# MZ.net
KiCad netlist of a schematic drawn in Altium Designer
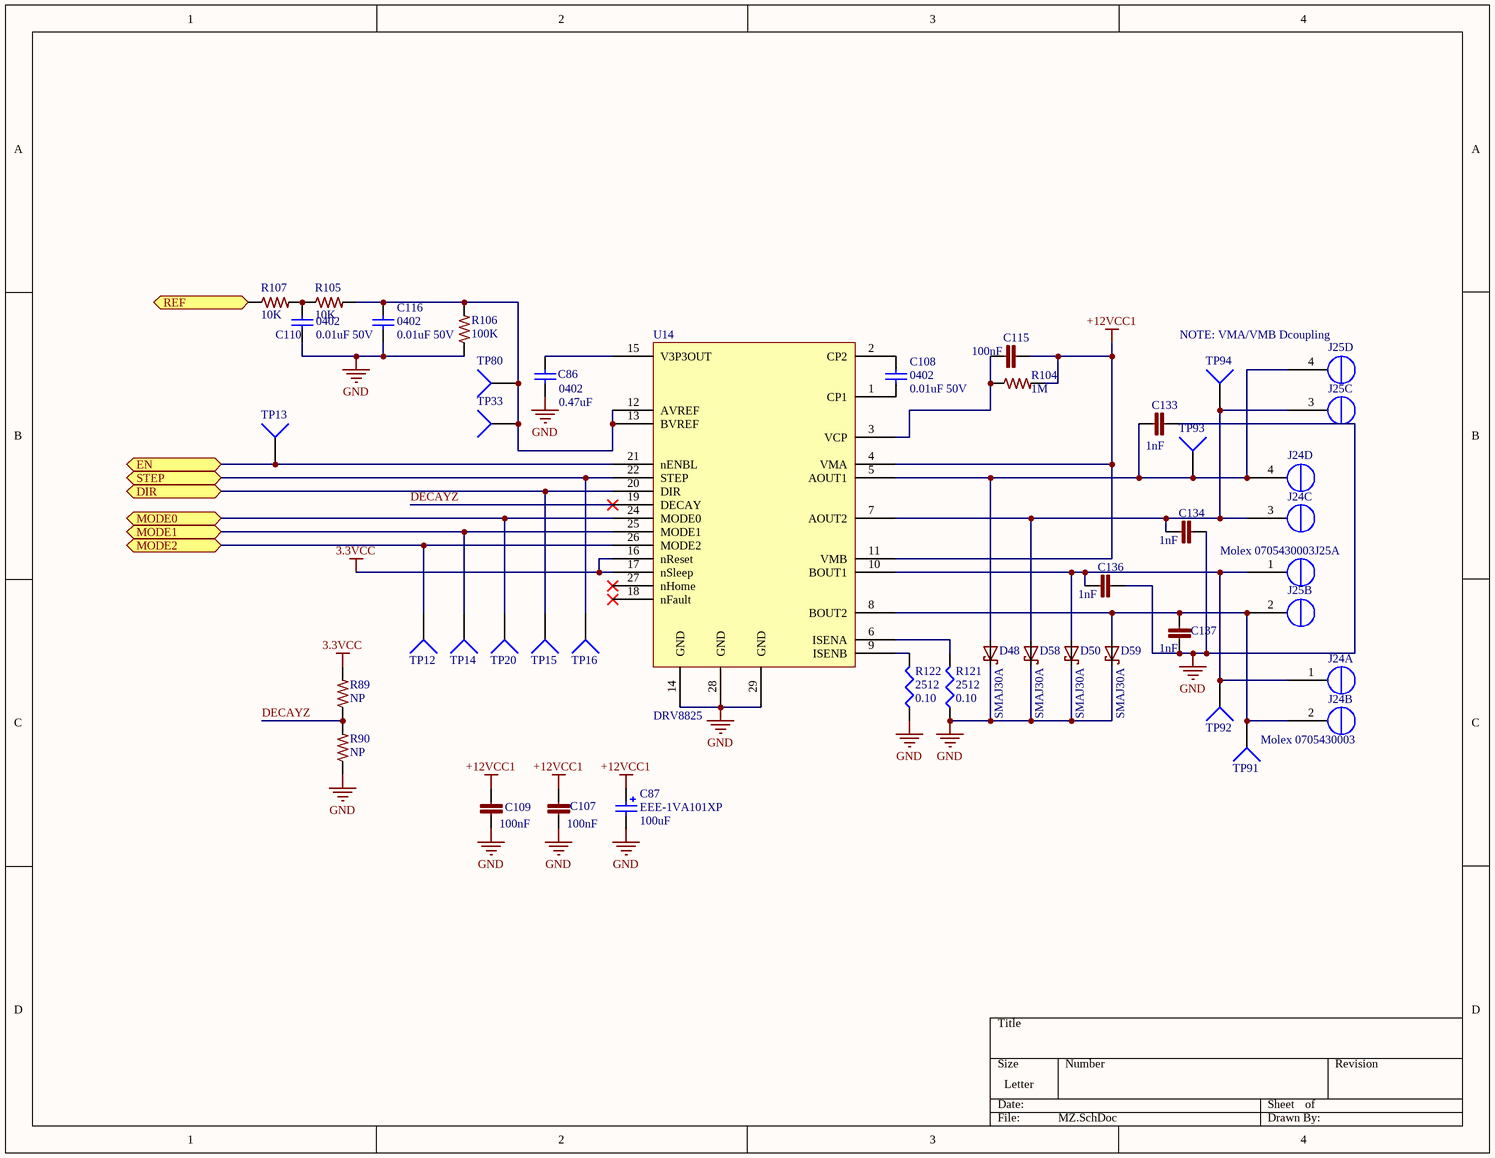
[diagram p0: MZ.SchDoc]

(export (version "E")
  (design (tool "Eeschema 10.0.6"))
  (components
    (comp (ref "C86")
      (value "0.47uF")
      (footprint "3Delight:C0402")
      (description "0.47uF 6.3v C0402 - GRM155R60J474KE19D")
      (fields
        (field (name "MFR PART #") "GRM155R60J474KE19D")
        (field (name "MFR") "Murata")
        (field (name "PACKAGEREFERENCE") "0402")
        (field (name "PUBLISHER") "Ultimachine")
      )
      (libsource (lib "Tigershark3D") (part "GRM155R60J474KE19D"))
    )
    (comp (ref "C87")
      (value "EEE-1VA101XP")
      (footprint "EEE-1VA101XP")
      (description "CAP ALUM 100UF 35V 20% SMD")
      (fields (field (name "DIGIKEY PART #") "PCE3951CT-ND") (field (name "ALTIUM_VALUE") "100uF"))
      (libsource (lib "Tigershark3D") (part "EEE-1VA101XP"))
    )
    (comp (ref "C107")
      (value "100nF")
      (footprint "C0603")
      (description "CAP CER 0603 100nF 50V 10% X7R")
      (fields
        (field (name "MANUFACTURERPARTNUMBER") "C0603C104K5RACTU")
        (field (name "PUBLISHER") "UltiMachine")
      )
      (libsource (lib "3Delight") (part "C0603C104K5RACTU"))
    )
    (comp (ref "C108")
      (value "0.01uF 50V")
      (footprint "C0402")
      (description "CAP CER 10000PF 50V X7R 0402")
      (fields
        (field (name "MFR PART #") "GRM155R71H103JA88D")
        (field (name "MFR") "Murata")
        (field (name "PACKAGEREFERENCE") "0402")
        (field (name "PUBLISHER") "Ultimachine")
      )
      (libsource (lib "Tigershark3D") (part "GRM155R71H103JA88D"))
    )
    (comp (ref "C109")
      (value "100nF")
      (footprint "C0603")
      (description "CAP CER 0603 100nF 50V 10% X7R")
      (fields
        (field (name "MANUFACTURERPARTNUMBER") "C0603C104K5RACTU")
        (field (name "PUBLISHER") "UltiMachine")
      )
      (libsource (lib "3Delight") (part "C0603C104K5RACTU"))
    )
    (comp (ref "C110")
      (value "0.01uF 50V")
      (footprint "C0402")
      (description "CAP CER 10000PF 50V X7R 0402")
      (fields
        (field (name "MFR PART #") "GRM155R71H103JA88D")
        (field (name "MFR") "Murata")
        (field (name "PACKAGEREFERENCE") "0402")
        (field (name "PUBLISHER") "Ultimachine")
      )
      (libsource (lib "Tigershark3D") (part "GRM155R71H103JA88D"))
    )
    (comp (ref "C115")
      (value "100nF")
      (footprint "C0402")
      (description "CAP CER 0402 100nF 16V 10% X7R")
      (fields
        (field (name "MANUFACTURERPARTNUMBER") "GRM155R71C104KA88D")
        (field (name "PUBLISHER") "UltiMachine")
      )
      (libsource (lib "3Delight") (part "GRM155R71C104KA88D"))
    )
    (comp (ref "C116")
      (value "0.01uF 50V")
      (footprint "C0402")
      (description "CAP CER 10000PF 50V X7R 0402")
      (fields
        (field (name "MFR PART #") "GRM155R71H103JA88D")
        (field (name "MFR") "Murata")
        (field (name "PACKAGEREFERENCE") "0402")
        (field (name "PUBLISHER") "Ultimachine")
      )
      (libsource (lib "Tigershark3D") (part "GRM155R71H103JA88D"))
    )
    (comp (ref "C133")
      (value "1nF")
      (footprint "C0603")
      (description "CAP CER 0603  1nF 50v 10% X7R")
      (fields
        (field (name "MANUFACTURERPARTNUMBER") "C0603C102K5RACTU")
        (field (name "PUBLISHER") "UltiMachine")
      )
      (libsource (lib "") (part "C0603C102K5RACTU_1"))
    )
    (comp (ref "C134")
      (value "1nF")
      (footprint "C0603")
      (description "CAP CER 0603  1nF 50v 10% X7R")
      (fields
        (field (name "MANUFACTURERPARTNUMBER") "C0603C102K5RACTU")
        (field (name "PUBLISHER") "UltiMachine")
      )
      (libsource (lib "") (part "C0603C102K5RACTU_1"))
    )
    (comp (ref "C136")
      (value "1nF")
      (footprint "C0603")
      (description "CAP CER 0603  1nF 50v 10% X7R")
      (fields
        (field (name "MANUFACTURERPARTNUMBER") "C0603C102K5RACTU")
        (field (name "PUBLISHER") "UltiMachine")
      )
      (libsource (lib "") (part "C0603C102K5RACTU_1"))
    )
    (comp (ref "C137")
      (value "1nF")
      (footprint "C0603")
      (description "CAP CER 0603  1nF 50v 10% X7R")
      (fields
        (field (name "MANUFACTURERPARTNUMBER") "C0603C102K5RACTU")
        (field (name "PUBLISHER") "UltiMachine")
      )
      (libsource (lib "3Delight") (part "C0603C102K5RACTU"))
    )
    (comp (ref "D48")
      (value "SMAJ30A")
      (footprint "SMA-SM")
      (description "DIODE TVS 30V SMA")
      (fields (field (name "PUBLISHER") "UltiMachine"))
      (libsource (lib "3Delight") (part "SMAJ30A"))
    )
    (comp (ref "D50")
      (value "SMAJ30A")
      (footprint "SMA-SM")
      (description "DIODE TVS 30V SMA")
      (fields (field (name "PUBLISHER") "UltiMachine"))
      (libsource (lib "3Delight") (part "SMAJ30A"))
    )
    (comp (ref "D58")
      (value "SMAJ30A")
      (footprint "SMA-SM")
      (description "DIODE TVS 30V SMA")
      (fields (field (name "PUBLISHER") "UltiMachine"))
      (libsource (lib "3Delight") (part "SMAJ30A"))
    )
    (comp (ref "D59")
      (value "SMAJ30A")
      (footprint "SMA-SM")
      (description "DIODE TVS 30V SMA")
      (fields (field (name "PUBLISHER") "UltiMachine"))
      (libsource (lib "3Delight") (part "SMAJ30A"))
    )
    (comp (ref "J24")
      (value "Molex 0705430003")
      (footprint "4POL254")
      (description "Molex 4 Pin Clip Connector")
      (libsource (lib "ZMBo Schematic Library") (part "Molex 0705430003 Alt"))
    )
    (comp (ref "J25")
      (value "Molex 0705430003")
      (footprint "4POL254")
      (description "Molex 4 Pin Clip Connector")
      (libsource (lib "ZMBo Schematic Library") (part "Molex 0705430003 Alt"))
    )
    (comp (ref "R89")
      (value "NP")
      (footprint "R0402")
      (description "Resistor")
      (fields (field (name "PUBLISHER") "UltiMachine"))
      (libsource (lib "3Delight") (part "Resistor"))
    )
    (comp (ref "R90")
      (value "NP")
      (footprint "R0402")
      (description "Resistor")
      (fields (field (name "PUBLISHER") "UltiMachine"))
      (libsource (lib "3Delight") (part "Resistor"))
    )
    (comp (ref "R104")
      (value "1M")
      (footprint "R0402")
      (description "RES 0402 1M 100mW 5%")
      (fields (field (name "MANUFACTURERPARTNUMBER") "ERJ2GEJ105X") (field (name "PUBLISHER") "UltiMachine"))
      (libsource (lib "3Delight") (part "ERJ2GEJ105X"))
    )
    (comp (ref "R105")
      (value "10K")
      (footprint "R0402")
      (description "RES SMD 10K OHM 1% 1/16W 0402")
      (fields
        (field (name "MANUFACTURERPARTNUMBER") "RC0402FR-0710KP")
        (field (name "PUBLISHER") "UltiMachine")
      )
      (libsource (lib "3Delight") (part "RC0402FR-0710KP"))
    )
    (comp (ref "R106")
      (value "100K")
      (footprint "R0402")
      (description "RES SMD 100K OHM 1% 1/16W 0402")
      (fields
        (field (name "MANUFACTURER") "Samsung")
        (field (name "MANUFACTURERPARTNUMBER") "RC1005F104CS")
        (field (name "PUBLISHER") "UltiMachine")
      )
      (libsource (lib "Tigershark3D") (part "RC1005F104CS"))
    )
    (comp (ref "R107")
      (value "10K")
      (footprint "R0402")
      (description "RES SMD 10K OHM 1% 1/16W 0402")
      (fields
        (field (name "MANUFACTURERPARTNUMBER") "RC0402FR-0710KP")
        (field (name "PUBLISHER") "UltiMachine")
      )
      (libsource (lib "3Delight") (part "RC0402FR-0710KP"))
    )
    (comp (ref "R121")
      (value "2512")
      (footprint "2512R-0.55")
      (description "RES SMD 0.1 OHM 1% 2W 2512")
      (fields (field (name "MFR") "Stackpole ELectronics Inc") (field (name "ALTIUM_VALUE") "0.10"))
      (libsource (lib "Tigershark3D") (part "CSRN2512FTR100"))
    )
    (comp (ref "R122")
      (value "2512")
      (footprint "2512R-0.55")
      (description "RES SMD 0.1 OHM 1% 2W 2512")
      (fields (field (name "MFR") "Stackpole ELectronics Inc") (field (name "ALTIUM_VALUE") "0.10"))
      (libsource (lib "Tigershark3D") (part "CSRN2512FTR100"))
    )
    (comp (ref "TP12")
      (value "TP4")
      (footprint "TP-2")
      (description "Socket")
      (fields (field (name "PUBLISHER") "Altium Limited"))
      (libsource (lib "ZMBo Schematic Library") (part "Socket"))
    )
    (comp (ref "TP13")
      (value "TP4")
      (footprint "TP-2")
      (description "Socket")
      (fields (field (name "PUBLISHER") "Altium Limited"))
      (libsource (lib "ZMBo Schematic Library") (part "Socket"))
    )
    (comp (ref "TP14")
      (value "TP4")
      (footprint "TP-2")
      (description "Socket")
      (fields (field (name "PUBLISHER") "Altium Limited"))
      (libsource (lib "ZMBo Schematic Library") (part "Socket"))
    )
    (comp (ref "TP15")
      (value "TP4")
      (footprint "TP-2")
      (description "Socket")
      (fields (field (name "PUBLISHER") "Altium Limited"))
      (libsource (lib "ZMBo Schematic Library") (part "Socket"))
    )
    (comp (ref "TP16")
      (value "TP4")
      (footprint "TP-2")
      (description "Socket")
      (fields (field (name "PUBLISHER") "Altium Limited"))
      (libsource (lib "ZMBo Schematic Library") (part "Socket"))
    )
    (comp (ref "TP20")
      (value "TP4")
      (footprint "TP-2")
      (description "Socket")
      (fields (field (name "PUBLISHER") "Altium Limited"))
      (libsource (lib "ZMBo Schematic Library") (part "Socket"))
    )
    (comp (ref "TP33")
      (value "TP4")
      (footprint "TP-2")
      (description "Socket")
      (fields (field (name "PUBLISHER") "Altium Limited"))
      (libsource (lib "ZMBo Schematic Library") (part "Socket"))
    )
    (comp (ref "TP80")
      (value "TP4")
      (footprint "TP-2")
      (description "Socket")
      (fields (field (name "PUBLISHER") "Altium Limited"))
      (libsource (lib "ZMBo Schematic Library") (part "Socket"))
    )
    (comp (ref "TP91")
      (value "TP4")
      (footprint "TP-2")
      (description "Socket")
      (fields (field (name "PUBLISHER") "Altium Limited"))
      (libsource (lib "ZMBo Schematic Library") (part "Socket"))
    )
    (comp (ref "TP92")
      (value "TP4")
      (footprint "TP-2")
      (description "Socket")
      (fields (field (name "PUBLISHER") "Altium Limited"))
      (libsource (lib "ZMBo Schematic Library") (part "Socket"))
    )
    (comp (ref "TP93")
      (value "TP4")
      (footprint "TP-2")
      (description "Socket")
      (fields (field (name "PUBLISHER") "Altium Limited"))
      (libsource (lib "ZMBo Schematic Library") (part "Socket"))
    )
    (comp (ref "TP94")
      (value "TP4")
      (footprint "TP-2")
      (description "Socket")
      (fields (field (name "PUBLISHER") "Altium Limited"))
      (libsource (lib "ZMBo Schematic Library") (part "Socket"))
    )
    (comp (ref "U14")
      (value "DRV8825")
      (footprint "DRV8825PWPR")
      (description "DRV8825 Ti Stepper Driver")
      (fields (field (name "PART NUMBER") "DRV8825PWPR") (field (name "VOLTAGE") "8.2-45VDC"))
      (libsource (lib "Tigershark3D") (part "DRV8825"))
    )
  )
  (nets
    (net (code "1") (name "+12VCC1") (class "Default")
      (node (ref "C107") (pin "1") (pinfunction "1_1") (pintype "passive"))
      (node (ref "C109") (pin "1") (pinfunction "1_1") (pintype "passive"))
      (node (ref "C115") (pin "2") (pinfunction "2_2") (pintype "passive"))
      (node (ref "C87") (pin "1") (pinfunction "1_1") (pintype "passive"))
      (node (ref "R104") (pin "2") (pinfunction "2_2") (pintype "passive"))
      (node (ref "U14") (pin "11") (pinfunction "VMB_11") (pintype "passive"))
      (node (ref "U14") (pin "4") (pinfunction "VMA_4") (pintype "passive"))
    )
    (net (code "2") (name "/DECAYZ") (class "Default")
      (node (ref "R89") (pin "1") (pinfunction "1_1") (pintype "passive"))
      (node (ref "R90") (pin "2") (pinfunction "2_2") (pintype "passive"))
      (node (ref "U14") (pin "19") (pinfunction "DECAY_19") (pintype "passive"))
    )
    (net (code "3") (name "/DIR") (class "Default")
      (node (ref "TP15") (pin "1") (pinfunction "1_1") (pintype "passive"))
      (node (ref "U14") (pin "20") (pinfunction "DIR_20") (pintype "passive"))
    )
    (net (code "4") (name "/EN") (class "Default")
      (node (ref "TP13") (pin "1") (pinfunction "1_1") (pintype "passive"))
      (node (ref "U14") (pin "21") (pinfunction "nENBL_21") (pintype "passive"))
    )
    (net (code "5") (name "/MODE0") (class "Default")
      (node (ref "TP20") (pin "1") (pinfunction "1_1") (pintype "passive"))
      (node (ref "U14") (pin "24") (pinfunction "MODE0_24") (pintype "passive"))
    )
    (net (code "6") (name "/MODE1") (class "Default")
      (node (ref "TP14") (pin "1") (pinfunction "1_1") (pintype "passive"))
      (node (ref "U14") (pin "25") (pinfunction "MODE1_25") (pintype "passive"))
    )
    (net (code "7") (name "/MODE2") (class "Default")
      (node (ref "TP12") (pin "1") (pinfunction "1_1") (pintype "passive"))
      (node (ref "U14") (pin "26") (pinfunction "MODE2_26") (pintype "passive"))
    )
    (net (code "8") (name "/REF") (class "Default")
      (node (ref "R107") (pin "1") (pinfunction "1_1") (pintype "passive"))
    )
    (net (code "9") (name "/STEP") (class "Default")
      (node (ref "TP16") (pin "1") (pinfunction "1_1") (pintype "passive"))
      (node (ref "U14") (pin "22") (pinfunction "STEP_22") (pintype "passive"))
    )
    (net (code "10") (name "3.3VCC") (class "Default")
      (node (ref "R89") (pin "2") (pinfunction "2_2") (pintype "passive"))
      (node (ref "U14") (pin "16") (pinfunction "nReset_16") (pintype "passive"))
      (node (ref "U14") (pin "17") (pinfunction "nSleep_17") (pintype "passive"))
    )
    (net (code "11") (name "GND") (class "Default")
      (node (ref "C107") (pin "2") (pinfunction "2_2") (pintype "passive"))
      (node (ref "C109") (pin "2") (pinfunction "2_2") (pintype "passive"))
      (node (ref "C110") (pin "1") (pinfunction "1_1") (pintype "passive"))
      (node (ref "C116") (pin "1") (pinfunction "1_1") (pintype "passive"))
      (node (ref "C133") (pin "2") (pinfunction "2_2") (pintype "passive"))
      (node (ref "C134") (pin "2") (pinfunction "2_2") (pintype "passive"))
      (node (ref "C136") (pin "2") (pinfunction "2_2") (pintype "passive"))
      (node (ref "C137") (pin "1") (pinfunction "1_1") (pintype "passive"))
      (node (ref "C86") (pin "1") (pinfunction "1_1") (pintype "passive"))
      (node (ref "C87") (pin "2") (pinfunction "2_2") (pintype "passive"))
      (node (ref "D48") (pin "C") (pinfunction "C_C") (pintype "passive"))
      (node (ref "D50") (pin "C") (pinfunction "C_C") (pintype "passive"))
      (node (ref "D58") (pin "C") (pinfunction "C_C") (pintype "passive"))
      (node (ref "D59") (pin "C") (pinfunction "C_C") (pintype "passive"))
      (node (ref "R106") (pin "1") (pinfunction "1_1") (pintype "passive"))
      (node (ref "R121") (pin "1") (pinfunction "1_1") (pintype "passive"))
      (node (ref "R122") (pin "1") (pinfunction "1_1") (pintype "passive"))
      (node (ref "R90") (pin "1") (pinfunction "1_1") (pintype "passive"))
      (node (ref "U14") (pin "14") (pinfunction "GND_14") (pintype "passive"))
      (node (ref "U14") (pin "28") (pinfunction "GND_28") (pintype "passive"))
      (node (ref "U14") (pin "29") (pinfunction "GND_29") (pintype "passive"))
    )
    (net (code "12") (name "Net-(C110-Pad2)") (class "Default")
      (node (ref "C110") (pin "2") (pinfunction "2_2") (pintype "passive"))
      (node (ref "R105") (pin "1") (pinfunction "1_1") (pintype "passive"))
      (node (ref "R107") (pin "2") (pinfunction "2_2") (pintype "passive"))
    )
    (net (code "13") (name "Net-(J24A-OUT2B)") (class "Default")
      (node (ref "C136") (pin "1") (pinfunction "1_1") (pintype "passive"))
      (node (ref "D50") (pin "A") (pinfunction "A_A") (pintype "passive"))
      (node (ref "J24") (pin "1") (pinfunction "OUT2B_1") (pintype "passive"))
      (node (ref "J25") (pin "1") (pinfunction "OUT2B_1") (pintype "passive"))
      (node (ref "TP92") (pin "1") (pinfunction "1_1") (pintype "passive"))
      (node (ref "U14") (pin "10") (pinfunction "BOUT1_10") (pintype "passive"))
    )
    (net (code "14") (name "Net-(J24B-OUT2A)") (class "Default")
      (node (ref "C137") (pin "2") (pinfunction "2_2") (pintype "passive"))
      (node (ref "D59") (pin "A") (pinfunction "A_A") (pintype "passive"))
      (node (ref "J24") (pin "2") (pinfunction "OUT2A_2") (pintype "passive"))
      (node (ref "J25") (pin "2") (pinfunction "OUT2A_2") (pintype "passive"))
      (node (ref "TP91") (pin "1") (pinfunction "1_1") (pintype "passive"))
      (node (ref "U14") (pin "8") (pinfunction "BOUT2_8") (pintype "passive"))
    )
    (net (code "15") (name "Net-(J24C-OUT1A)") (class "Default")
      (node (ref "C134") (pin "1") (pinfunction "1_1") (pintype "passive"))
      (node (ref "D58") (pin "A") (pinfunction "A_A") (pintype "passive"))
      (node (ref "J24") (pin "3") (pinfunction "OUT1A_3") (pintype "passive"))
      (node (ref "J25") (pin "3") (pinfunction "OUT1A_3") (pintype "passive"))
      (node (ref "TP94") (pin "1") (pinfunction "1_1") (pintype "passive"))
      (node (ref "U14") (pin "7") (pinfunction "AOUT2_7") (pintype "passive"))
    )
    (net (code "16") (name "Net-(J24D-OUT1B)") (class "Default")
      (node (ref "C133") (pin "1") (pinfunction "1_1") (pintype "passive"))
      (node (ref "D48") (pin "A") (pinfunction "A_A") (pintype "passive"))
      (node (ref "J24") (pin "4") (pinfunction "OUT1B_4") (pintype "passive"))
      (node (ref "J25") (pin "4") (pinfunction "OUT1B_4") (pintype "passive"))
      (node (ref "TP93") (pin "1") (pinfunction "1_1") (pintype "passive"))
      (node (ref "U14") (pin "5") (pinfunction "AOUT1_5") (pintype "passive"))
    )
    (net (code "17") (name "Net-(U14-AVREF)") (class "Default")
      (node (ref "C116") (pin "2") (pinfunction "2_2") (pintype "passive"))
      (node (ref "R105") (pin "2") (pinfunction "2_2") (pintype "passive"))
      (node (ref "R106") (pin "2") (pinfunction "2_2") (pintype "passive"))
      (node (ref "TP33") (pin "1") (pinfunction "1_1") (pintype "passive"))
      (node (ref "TP80") (pin "1") (pinfunction "1_1") (pintype "passive"))
      (node (ref "U14") (pin "12") (pinfunction "AVREF_12") (pintype "passive"))
      (node (ref "U14") (pin "13") (pinfunction "BVREF_13") (pintype "passive"))
    )
    (net (code "18") (name "Net-(U14-CP1)") (class "Default")
      (node (ref "C108") (pin "1") (pinfunction "1_1") (pintype "passive"))
      (node (ref "U14") (pin "1") (pinfunction "CP1_1") (pintype "passive"))
    )
    (net (code "19") (name "Net-(U14-CP2)") (class "Default")
      (node (ref "C108") (pin "2") (pinfunction "2_2") (pintype "passive"))
      (node (ref "U14") (pin "2") (pinfunction "CP2_2") (pintype "passive"))
    )
    (net (code "20") (name "Net-(U14-ISENA)") (class "Default")
      (node (ref "R121") (pin "2") (pinfunction "2_2") (pintype "passive"))
      (node (ref "U14") (pin "6") (pinfunction "ISENA_6") (pintype "passive"))
    )
    (net (code "21") (name "Net-(U14-ISENB)") (class "Default")
      (node (ref "R122") (pin "2") (pinfunction "2_2") (pintype "passive"))
      (node (ref "U14") (pin "9") (pinfunction "ISENB_9") (pintype "passive"))
    )
    (net (code "22") (name "Net-(U14-V3P3OUT)") (class "Default")
      (node (ref "C86") (pin "2") (pinfunction "2_2") (pintype "passive"))
      (node (ref "U14") (pin "15") (pinfunction "V3P3OUT_15") (pintype "passive"))
    )
    (net (code "23") (name "Net-(U14-VCP)") (class "Default")
      (node (ref "C115") (pin "1") (pinfunction "1_1") (pintype "passive"))
      (node (ref "R104") (pin "1") (pinfunction "1_1") (pintype "passive"))
      (node (ref "U14") (pin "3") (pinfunction "VCP_3") (pintype "passive"))
    )
    (net (code "24") (name "unconnected-(U14-NC-Pad23)") (class "Default")
      (node (ref "U14") (pin "23") (pinfunction "NC_23") (pintype "passive"))
    )
    (net (code "25") (name "unconnected-(U14-nFault-Pad18)") (class "Default")
      (node (ref "U14") (pin "18") (pinfunction "nFault_18") (pintype "passive+no_connect"))
    )
    (net (code "26") (name "unconnected-(U14-nHome-Pad27)") (class "Default")
      (node (ref "U14") (pin "27") (pinfunction "nHome_27") (pintype "passive+no_connect"))
    )
  )
)
